# blackfin_e_lcd_keypad.net
KiCad netlist of a schematic drawn in Altium Designer
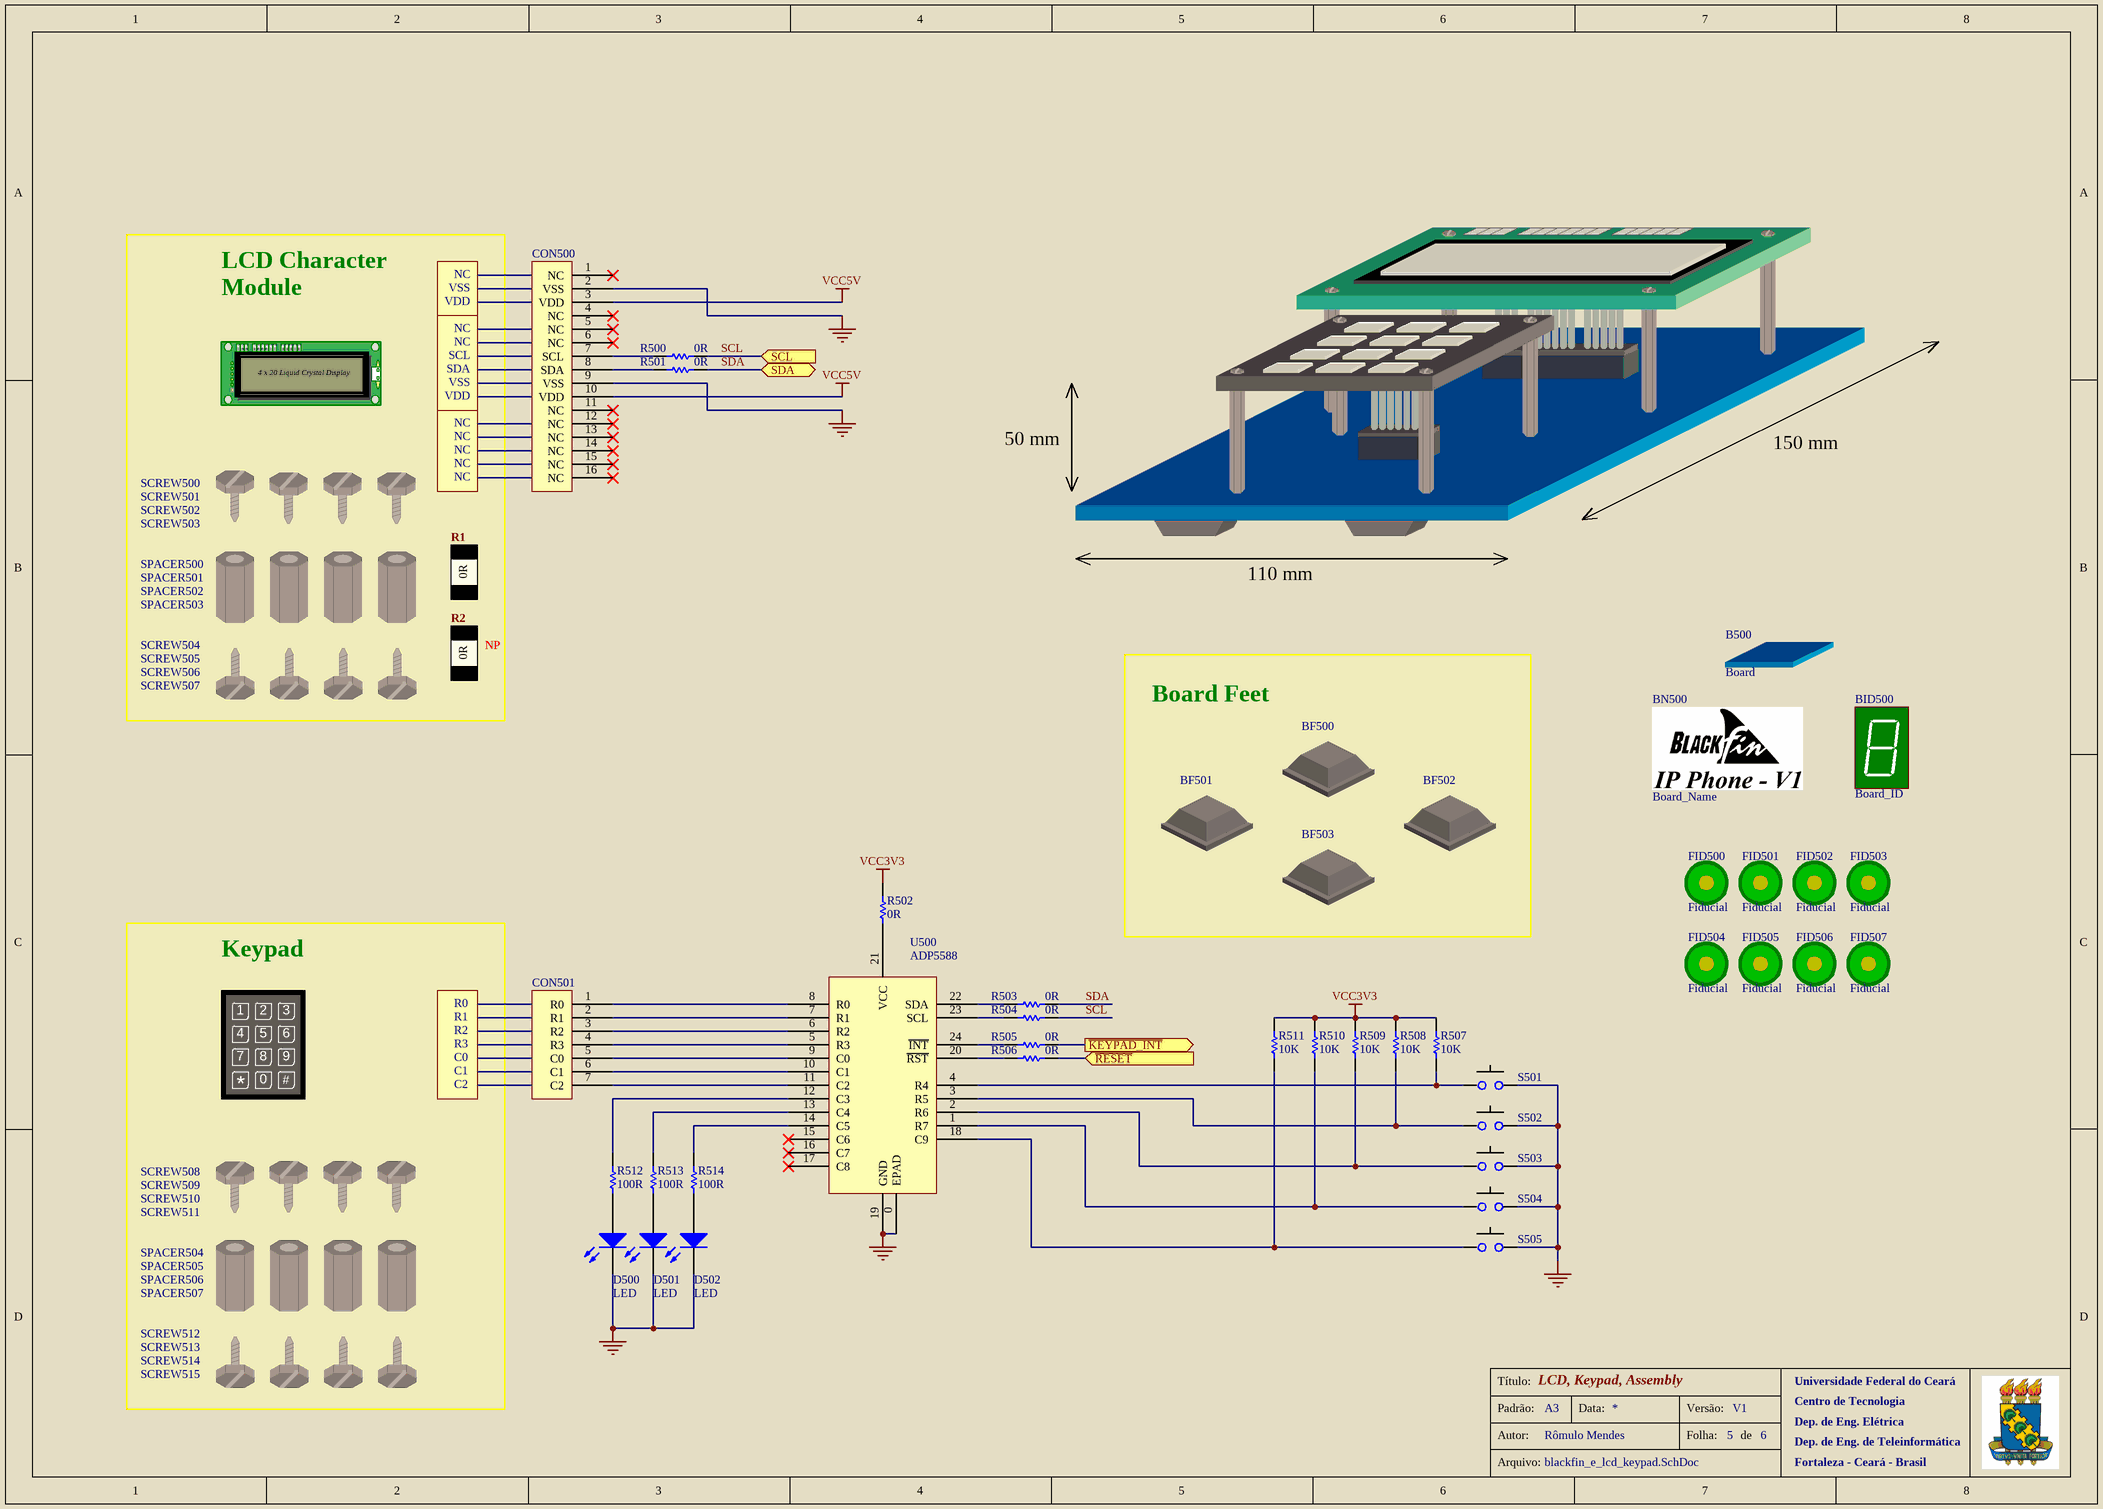
[diagram p0: blackfin_e_lcd_keypad.SchDoc]

(export (version "E")
  (design (tool "Eeschema 10.0.6"))
  (components
    (comp (ref "B500")
      (value "Board")
      (fields (field (name "EVENDORPART#") "NÃO SE APLICA"))
      (libsource (lib "blackfin_schlib") (part "Board"))
    )
    (comp (ref "BF500")
      (value "Board Foot")
      (footprint "blackfin_pcblib:Board Foot (Hemisphere)")
      (fields
        (field (name "EVENDORPART#") "517-SJ-5003BK")
        (field (name "PART#") "SJ-5003 (BLACK)")
        (field (name "MANUFACTURER") "3M Electronic Specialty")
      )
      (libsource (lib "*") (part "Board Foot"))
    )
    (comp (ref "BF501")
      (value "Board Foot")
      (footprint "blackfin_pcblib:Board Foot (Hemisphere)")
      (fields
        (field (name "EVENDORPART#") "517-SJ-5003BK")
        (field (name "PART#") "SJ-5003 (BLACK)")
        (field (name "MANUFACTURER") "3M Electronic Specialty")
      )
      (libsource (lib "*") (part "Board Foot"))
    )
    (comp (ref "BF502")
      (value "Board Foot")
      (footprint "blackfin_pcblib:Board Foot (Hemisphere)")
      (fields
        (field (name "EVENDORPART#") "517-SJ-5003BK")
        (field (name "PART#") "SJ-5003 (BLACK)")
        (field (name "MANUFACTURER") "3M Electronic Specialty")
      )
      (libsource (lib "*") (part "Board Foot"))
    )
    (comp (ref "BF503")
      (value "Board Foot")
      (footprint "blackfin_pcblib:Board Foot (Hemisphere)")
      (fields
        (field (name "EVENDORPART#") "517-SJ-5003BK")
        (field (name "PART#") "SJ-5003 (BLACK)")
        (field (name "MANUFACTURER") "3M Electronic Specialty")
      )
      (libsource (lib "*") (part "Board Foot"))
    )
    (comp (ref "BID500")
      (value "Board_ID")
      (footprint "blackfin_pcblib:BOARD_ID")
      (fields (field (name "EVENDORPART#") "NÃO SE APLICA"))
      (libsource (lib "blackfin_schlib") (part "Board_ID"))
    )
    (comp (ref "BN500")
      (value "Board_Name")
      (footprint "blackfin_pcblib:LOGO")
      (fields (field (name "EVENDORPART#") "NÃO SE APLICA"))
      (libsource (lib "blackfin_schlib") (part "Board_Name"))
    )
    (comp (ref "CON500")
      (value "LCD_Connector")
      (footprint "blackfin_pcblib:SOCKET_1x16")
      (fields (field (name "EVENDORPART#") "SSM-116-L-SV") (field (name "MANUFACTURER") "Samtec"))
      (libsource (lib "blackfin_schlib") (part "LCD_Connector"))
    )
    (comp (ref "CON501")
      (value "Keypad_Connector")
      (footprint "blackfin_pcblib:SOCKET_1x7")
      (fields (field (name "EVENDORPART#") "SSM-107-L-SV") (field (name "MANUFACTURER") "Samtec"))
      (libsource (lib "blackfin_schlib") (part "Keypad_Connector"))
    )
    (comp (ref "D500")
      (value "LED")
      (footprint "blackfin_pcblib:LED_0603")
      (description "Red LED")
      (fields (field (name "EVENDORPART#") "638-QTLP600C2TR") (field (name "MANUFACTURER") "Everlight"))
      (libsource (lib "blackfin_schlib") (part "LED"))
    )
    (comp (ref "D501")
      (value "LED")
      (footprint "blackfin_pcblib:LED_0603")
      (description "Red LED")
      (fields (field (name "EVENDORPART#") "638-QTLP600C2TR") (field (name "MANUFACTURER") "Everlight"))
      (libsource (lib "blackfin_schlib") (part "LED"))
    )
    (comp (ref "D502")
      (value "LED")
      (footprint "blackfin_pcblib:LED_0603")
      (description "Red LED")
      (fields (field (name "EVENDORPART#") "638-QTLP600C2TR") (field (name "MANUFACTURER") "Everlight"))
      (libsource (lib "blackfin_schlib") (part "LED"))
    )
    (comp (ref "FID500")
      (value "Fiducial")
      (footprint "blackfin_pcblib:Fiducial")
      (fields (field (name "EVENDORPART#") "NÃO SE APLICA"))
      (libsource (lib "blackfin_schlib") (part "Fiducial"))
    )
    (comp (ref "FID501")
      (value "Fiducial")
      (footprint "blackfin_pcblib:Fiducial")
      (fields (field (name "EVENDORPART#") "NÃO SE APLICA"))
      (libsource (lib "blackfin_schlib") (part "Fiducial"))
    )
    (comp (ref "FID502")
      (value "Fiducial")
      (footprint "blackfin_pcblib:Fiducial")
      (fields (field (name "EVENDORPART#") "NÃO SE APLICA"))
      (libsource (lib "blackfin_schlib") (part "Fiducial"))
    )
    (comp (ref "FID503")
      (value "Fiducial")
      (footprint "blackfin_pcblib:Fiducial")
      (fields (field (name "EVENDORPART#") "NÃO SE APLICA"))
      (libsource (lib "blackfin_schlib") (part "Fiducial"))
    )
    (comp (ref "FID504")
      (value "Fiducial")
      (footprint "blackfin_pcblib:Fiducial")
      (fields (field (name "EVENDORPART#") "NÃO SE APLICA"))
      (libsource (lib "blackfin_schlib") (part "Fiducial"))
    )
    (comp (ref "FID505")
      (value "Fiducial")
      (footprint "blackfin_pcblib:Fiducial")
      (fields (field (name "EVENDORPART#") "NÃO SE APLICA"))
      (libsource (lib "blackfin_schlib") (part "Fiducial"))
    )
    (comp (ref "FID506")
      (value "Fiducial")
      (footprint "blackfin_pcblib:Fiducial")
      (fields (field (name "EVENDORPART#") "NÃO SE APLICA"))
      (libsource (lib "blackfin_schlib") (part "Fiducial"))
    )
    (comp (ref "FID507")
      (value "Fiducial")
      (footprint "blackfin_pcblib:Fiducial")
      (fields (field (name "EVENDORPART#") "NÃO SE APLICA"))
      (libsource (lib "blackfin_schlib") (part "Fiducial"))
    )
    (comp (ref "KEYPAD_HEADER500")
      (value "Keypad_Header_1x7")
      (fields (field (name "EVENDORPART#") "ESQ-107-34-L-S") (field (name "MANUFACTURER") "Samtec"))
      (libsource (lib "blackfin_schlib") (part "Keypad_Header_1x7"))
    )
    (comp (ref "LCD500")
      (value "LCD")
      (footprint "blackfin_pcblib:LCD")
      (fields
        (field (name "EVENDORPART#") "763-0420D3Z-FL-GBW")
        (field (name "PART#") "NHD-0420D3Z-FL-GBW")
        (field (name "MANUFACTURER") "Newhaven")
      )
      (libsource (lib "*") (part "LCD"))
    )
    (comp (ref "LCD_HEADER500")
      (value "LCD_Header_1x3")
      (fields (field (name "EVENDORPART#") "DW-03-12-F-S-694") (field (name "MANUFACTURER") "Samtec"))
      (libsource (lib "blackfin_schlib") (part "LCD_Header_1x3"))
    )
    (comp (ref "LCD_HEADER501")
      (value "LCD_Header_1x6")
      (fields (field (name "EVENDORPART#") "DW-06-12-F-S-694") (field (name "MANUFACTURER") "Samtec"))
      (libsource (lib "blackfin_schlib") (part "LCD_Header_1x6"))
    )
    (comp (ref "LCD_HEADER502")
      (value "LCD_Header_1x5")
      (fields (field (name "EVENDORPART#") "DW-05-12-F-S-694") (field (name "MANUFACTURER") "Samtec"))
      (libsource (lib "blackfin_schlib") (part "LCD_Header_1x5"))
    )
    (comp (ref "LCD_RES500")
      (value "LCD_Resistor")
      (fields
        (field (name "EVENDORPART#") "71-CRCW0805-0-E3")
        (field (name "MANUFACTURER") "Vishay/Dale")
        (field (name "PART#") "CRCW08050000Z0EA")
      )
      (libsource (lib "blackfin_schlib") (part "LCD_Resistor"))
    )
    (comp (ref "LCD_RES501")
      (value "LCD_Resistor")
      (fields
        (field (name "EVENDORPART#") "71-CRCW0805-0-E3")
        (field (name "MANUFACTURER") "Vishay/Dale")
        (field (name "PART#") "CRCW08050000Z0EA")
      )
      (libsource (lib "blackfin_schlib") (part "LCD_Resistor"))
    )
    (comp (ref "R500")
      (value "0R")
      (footprint "blackfin_pcblib:R_0603")
      (fields
        (field (name "EVENDORPART#") "71-CRCW06030000Z0EB")
        (field (name "PART#") "CRCW06030000Z0EB")
        (field (name "MANUFACTURER") "Vishay/Dale")
      )
      (libsource (lib "blackfin_schlib") (part "Resistor"))
    )
    (comp (ref "R501")
      (value "0R")
      (footprint "blackfin_pcblib:R_0603")
      (fields
        (field (name "EVENDORPART#") "71-CRCW06030000Z0EB")
        (field (name "PART#") "CRCW06030000Z0EB")
        (field (name "MANUFACTURER") "Vishay/Dale")
      )
      (libsource (lib "blackfin_schlib") (part "Resistor"))
    )
    (comp (ref "R502")
      (value "0R")
      (footprint "blackfin_pcblib:R_0603")
      (fields
        (field (name "EVENDORPART#") "71-CRCW06030000Z0EB")
        (field (name "PART#") "CRCW06030000Z0EB")
        (field (name "MANUFACTURER") "Vishay/Dale")
      )
      (libsource (lib "blackfin_schlib") (part "Resistor"))
    )
    (comp (ref "R503")
      (value "0R")
      (footprint "blackfin_pcblib:R_0603")
      (fields
        (field (name "EVENDORPART#") "71-CRCW06030000Z0EB")
        (field (name "PART#") "CRCW06030000Z0EB")
        (field (name "MANUFACTURER") "Vishay/Dale")
      )
      (libsource (lib "blackfin_schlib") (part "Resistor"))
    )
    (comp (ref "R504")
      (value "0R")
      (footprint "blackfin_pcblib:R_0603")
      (fields
        (field (name "EVENDORPART#") "71-CRCW06030000Z0EB")
        (field (name "PART#") "CRCW06030000Z0EB")
        (field (name "MANUFACTURER") "Vishay/Dale")
      )
      (libsource (lib "blackfin_schlib") (part "Resistor"))
    )
    (comp (ref "R505")
      (value "0R")
      (footprint "blackfin_pcblib:R_0603")
      (fields
        (field (name "EVENDORPART#") "71-CRCW06030000Z0EB")
        (field (name "PART#") "CRCW06030000Z0EB")
        (field (name "MANUFACTURER") "Vishay/Dale")
      )
      (libsource (lib "blackfin_schlib") (part "Resistor"))
    )
    (comp (ref "R506")
      (value "0R")
      (footprint "blackfin_pcblib:R_0603")
      (fields
        (field (name "EVENDORPART#") "71-CRCW06030000Z0EB")
        (field (name "PART#") "CRCW06030000Z0EB")
        (field (name "MANUFACTURER") "Vishay/Dale")
      )
      (libsource (lib "blackfin_schlib") (part "Resistor"))
    )
    (comp (ref "R507")
      (value "10K")
      (footprint "blackfin_pcblib:R_0603")
      (fields
        (field (name "EVENDORPART#") "71-CRCW0603-10K-E3")
        (field (name "PART#") "CRCW060310K0FKEA")
        (field (name "MANUFACTURER") "Vishay/Dale")
      )
      (libsource (lib "blackfin_schlib") (part "Resistor"))
    )
    (comp (ref "R508")
      (value "10K")
      (footprint "blackfin_pcblib:R_0603")
      (fields
        (field (name "EVENDORPART#") "71-CRCW0603-10K-E3")
        (field (name "PART#") "CRCW060310K0FKEA")
        (field (name "MANUFACTURER") "Vishay/Dale")
      )
      (libsource (lib "blackfin_schlib") (part "Resistor"))
    )
    (comp (ref "R509")
      (value "10K")
      (footprint "blackfin_pcblib:R_0603")
      (fields
        (field (name "EVENDORPART#") "71-CRCW0603-10K-E3")
        (field (name "PART#") "CRCW060310K0FKEA")
        (field (name "MANUFACTURER") "Vishay/Dale")
      )
      (libsource (lib "blackfin_schlib") (part "Resistor"))
    )
    (comp (ref "R510")
      (value "10K")
      (footprint "blackfin_pcblib:R_0603")
      (fields
        (field (name "EVENDORPART#") "71-CRCW0603-10K-E3")
        (field (name "PART#") "CRCW060310K0FKEA")
        (field (name "MANUFACTURER") "Vishay/Dale")
      )
      (libsource (lib "blackfin_schlib") (part "Resistor"))
    )
    (comp (ref "R511")
      (value "10K")
      (footprint "blackfin_pcblib:R_0603")
      (fields
        (field (name "EVENDORPART#") "71-CRCW0603-10K-E3")
        (field (name "PART#") "CRCW060310K0FKEA")
        (field (name "MANUFACTURER") "Vishay/Dale")
      )
      (libsource (lib "blackfin_schlib") (part "Resistor"))
    )
    (comp (ref "R512")
      (value "100R")
      (footprint "blackfin_pcblib:R_0603")
      (fields
        (field (name "EVENDORPART#") "71-CRCW0603-100-E3")
        (field (name "PART#") "CRCW0603100RFKEA")
        (field (name "MANUFACTURER") "Vishay/Dale")
      )
      (libsource (lib "blackfin_schlib") (part "Resistor"))
    )
    (comp (ref "R513")
      (value "100R")
      (footprint "blackfin_pcblib:R_0603")
      (fields
        (field (name "EVENDORPART#") "71-CRCW0603-100-E3")
        (field (name "PART#") "CRCW0603100RFKEA")
        (field (name "MANUFACTURER") "Vishay/Dale")
      )
      (libsource (lib "blackfin_schlib") (part "Resistor"))
    )
    (comp (ref "R514")
      (value "100R")
      (footprint "blackfin_pcblib:R_0603")
      (fields
        (field (name "EVENDORPART#") "71-CRCW0603-100-E3")
        (field (name "PART#") "CRCW0603100RFKEA")
        (field (name "MANUFACTURER") "Vishay/Dale")
      )
      (libsource (lib "blackfin_schlib") (part "Resistor"))
    )
    (comp (ref "S500")
      (value "Keypad")
      (footprint "blackfin_pcblib:Keypad")
      (fields
        (field (name "EVENDORPART#") "GH5009-ND")
        (field (name "PART#") "96AB2-152-R")
        (field (name "MANUFACTURER") "Grayhill Inc")
      )
      (libsource (lib "blackfin_schlib") (part "Keypad"))
    )
    (comp (ref "S501")
      (value "Push Button")
      (footprint "blackfin_pcblib:Push Button")
      (fields
        (field (name "EVENDORPART#") "611-PTS645SH50SMTRLF")
        (field (name "PART#") "PTS645SH50SMTRLFS")
        (field (name "MANUFACTURER") "C&K Components")
      )
      (libsource (lib "*") (part "Push Button"))
    )
    (comp (ref "S502")
      (value "Push Button")
      (footprint "blackfin_pcblib:Push Button")
      (fields
        (field (name "EVENDORPART#") "611-PTS645SH50SMTRLF")
        (field (name "PART#") "PTS645SH50SMTRLFS")
        (field (name "MANUFACTURER") "C&K Components")
      )
      (libsource (lib "*") (part "Push Button"))
    )
    (comp (ref "S503")
      (value "Push Button")
      (footprint "blackfin_pcblib:Push Button")
      (fields
        (field (name "EVENDORPART#") "611-PTS645SH50SMTRLF")
        (field (name "PART#") "PTS645SH50SMTRLFS")
        (field (name "MANUFACTURER") "C&K Components")
      )
      (libsource (lib "*") (part "Push Button"))
    )
    (comp (ref "S504")
      (value "Push Button")
      (footprint "blackfin_pcblib:Push Button")
      (fields
        (field (name "EVENDORPART#") "611-PTS645SH50SMTRLF")
        (field (name "PART#") "PTS645SH50SMTRLFS")
        (field (name "MANUFACTURER") "C&K Components")
      )
      (libsource (lib "*") (part "Push Button"))
    )
    (comp (ref "S505")
      (value "Push Button")
      (footprint "blackfin_pcblib:Push Button")
      (fields
        (field (name "EVENDORPART#") "611-PTS645SH50SMTRLF")
        (field (name "PART#") "PTS645SH50SMTRLFS")
        (field (name "MANUFACTURER") "C&K Components")
      )
      (libsource (lib "*") (part "Push Button"))
    )
    (comp (ref "SCREW500")
      (value "Screw")
      (fields
        (field (name "EVENDORPART#") "534-29301")
        (field (name "PART#") "29301")
        (field (name "MANUFACTURER") "Keystone Electronics")
      )
      (libsource (lib "*") (part "Screw"))
    )
    (comp (ref "SCREW501")
      (value "Screw")
      (fields
        (field (name "EVENDORPART#") "534-29301")
        (field (name "PART#") "29301")
        (field (name "MANUFACTURER") "Keystone Electronics")
      )
      (libsource (lib "*") (part "Screw"))
    )
    (comp (ref "SCREW502")
      (value "Screw")
      (fields
        (field (name "EVENDORPART#") "534-29301")
        (field (name "PART#") "29301")
        (field (name "MANUFACTURER") "Keystone Electronics")
      )
      (libsource (lib "*") (part "Screw"))
    )
    (comp (ref "SCREW503")
      (value "Screw")
      (fields
        (field (name "EVENDORPART#") "534-29301")
        (field (name "PART#") "29301")
        (field (name "MANUFACTURER") "Keystone Electronics")
      )
      (libsource (lib "*") (part "Screw"))
    )
    (comp (ref "SCREW504")
      (value "Screw")
      (fields
        (field (name "EVENDORPART#") "534-29301")
        (field (name "PART#") "29301")
        (field (name "MANUFACTURER") "Keystone Electronics")
      )
      (libsource (lib "*") (part "Screw"))
    )
    (comp (ref "SCREW505")
      (value "Screw")
      (fields
        (field (name "EVENDORPART#") "534-29301")
        (field (name "PART#") "29301")
        (field (name "MANUFACTURER") "Keystone Electronics")
      )
      (libsource (lib "*") (part "Screw"))
    )
    (comp (ref "SCREW506")
      (value "Screw")
      (fields
        (field (name "EVENDORPART#") "534-29301")
        (field (name "PART#") "29301")
        (field (name "MANUFACTURER") "Keystone Electronics")
      )
      (libsource (lib "*") (part "Screw"))
    )
    (comp (ref "SCREW507")
      (value "Screw")
      (fields
        (field (name "EVENDORPART#") "534-29301")
        (field (name "PART#") "29301")
        (field (name "MANUFACTURER") "Keystone Electronics")
      )
      (libsource (lib "*") (part "Screw"))
    )
    (comp (ref "SCREW508")
      (value "Screw")
      (fields
        (field (name "EVENDORPART#") "534-29301")
        (field (name "PART#") "29301")
        (field (name "MANUFACTURER") "Keystone Electronics")
      )
      (libsource (lib "*") (part "Screw"))
    )
    (comp (ref "SCREW509")
      (value "Screw")
      (fields
        (field (name "EVENDORPART#") "534-29301")
        (field (name "PART#") "29301")
        (field (name "MANUFACTURER") "Keystone Electronics")
      )
      (libsource (lib "*") (part "Screw"))
    )
    (comp (ref "SCREW510")
      (value "Screw")
      (fields
        (field (name "EVENDORPART#") "534-29301")
        (field (name "PART#") "29301")
        (field (name "MANUFACTURER") "Keystone Electronics")
      )
      (libsource (lib "*") (part "Screw"))
    )
    (comp (ref "SCREW511")
      (value "Screw")
      (fields
        (field (name "EVENDORPART#") "534-29301")
        (field (name "PART#") "29301")
        (field (name "MANUFACTURER") "Keystone Electronics")
      )
      (libsource (lib "*") (part "Screw"))
    )
    (comp (ref "SCREW512")
      (value "Screw")
      (fields
        (field (name "EVENDORPART#") "534-29301")
        (field (name "PART#") "29301")
        (field (name "MANUFACTURER") "Keystone Electronics")
      )
      (libsource (lib "*") (part "Screw"))
    )
    (comp (ref "SCREW513")
      (value "Screw")
      (fields
        (field (name "EVENDORPART#") "534-29301")
        (field (name "PART#") "29301")
        (field (name "MANUFACTURER") "Keystone Electronics")
      )
      (libsource (lib "*") (part "Screw"))
    )
    (comp (ref "SCREW514")
      (value "Screw")
      (fields
        (field (name "EVENDORPART#") "534-29301")
        (field (name "PART#") "29301")
        (field (name "MANUFACTURER") "Keystone Electronics")
      )
      (libsource (lib "*") (part "Screw"))
    )
    (comp (ref "SCREW515")
      (value "Screw")
      (fields
        (field (name "EVENDORPART#") "534-29301")
        (field (name "PART#") "29301")
        (field (name "MANUFACTURER") "Keystone Electronics")
      )
      (libsource (lib "*") (part "Screw"))
    )
    (comp (ref "SPACER500")
      (value "Spacer")
      (fields
        (field (name "EVENDORPART#") "534-24428")
        (field (name "MANUFACTURER") "Keystone Electronics")
        (field (name "PART#") "24428")
      )
      (libsource (lib "blackfin_schlib") (part "Spacer"))
    )
    (comp (ref "SPACER501")
      (value "Spacer")
      (fields
        (field (name "EVENDORPART#") "534-24428")
        (field (name "MANUFACTURER") "Keystone Electronics")
        (field (name "PART#") "24428")
      )
      (libsource (lib "blackfin_schlib") (part "Spacer"))
    )
    (comp (ref "SPACER502")
      (value "Spacer")
      (fields
        (field (name "EVENDORPART#") "534-24428")
        (field (name "MANUFACTURER") "Keystone Electronics")
        (field (name "PART#") "24428")
      )
      (libsource (lib "blackfin_schlib") (part "Spacer"))
    )
    (comp (ref "SPACER503")
      (value "Spacer")
      (fields
        (field (name "EVENDORPART#") "534-24428")
        (field (name "MANUFACTURER") "Keystone Electronics")
        (field (name "PART#") "24428")
      )
      (libsource (lib "blackfin_schlib") (part "Spacer"))
    )
    (comp (ref "SPACER504")
      (value "Spacer")
      (fields
        (field (name "EVENDORPART#") "534-24428")
        (field (name "MANUFACTURER") "Keystone Electronics")
        (field (name "PART#") "24428")
      )
      (libsource (lib "blackfin_schlib") (part "Spacer"))
    )
    (comp (ref "SPACER505")
      (value "Spacer")
      (fields
        (field (name "EVENDORPART#") "534-24428")
        (field (name "MANUFACTURER") "Keystone Electronics")
        (field (name "PART#") "24428")
      )
      (libsource (lib "blackfin_schlib") (part "Spacer"))
    )
    (comp (ref "SPACER506")
      (value "Spacer")
      (fields
        (field (name "EVENDORPART#") "534-24428")
        (field (name "MANUFACTURER") "Keystone Electronics")
        (field (name "PART#") "24428")
      )
      (libsource (lib "blackfin_schlib") (part "Spacer"))
    )
    (comp (ref "SPACER507")
      (value "Spacer")
      (fields
        (field (name "EVENDORPART#") "534-24428")
        (field (name "MANUFACTURER") "Keystone Electronics")
        (field (name "PART#") "24428")
      )
      (libsource (lib "blackfin_schlib") (part "Spacer"))
    )
    (comp (ref "U500")
      (value "ADP5588")
      (footprint "blackfin_pcblib:QFN-24")
      (fields
        (field (name "EVENDORPART#") "ADP5588ACPZ-R7CT-ND")
        (field (name "PART#") "ADP5588ACPZ-R7")
        (field (name "MANUFACTURER") "Analog Devices")
      )
      (libsource (lib "blackfin_schlib") (part "ADP5588"))
    )
  )
  (nets
    (net (code "1") (name "/SCL") (class "Default")
      (node (ref "R500") (pin "2") (pinfunction "2_2") (pintype "passive"))
      (node (ref "R504") (pin "2") (pinfunction "2_2") (pintype "passive"))
    )
    (net (code "2") (name "/SDA") (class "Default")
      (node (ref "R501") (pin "2") (pinfunction "2_2") (pintype "passive"))
      (node (ref "R503") (pin "2") (pinfunction "2_2") (pintype "passive"))
    )
    (net (code "3") (name "/~{KEYPAD_INT}") (class "Default")
      (node (ref "R505") (pin "2") (pinfunction "2_2") (pintype "passive"))
    )
    (net (code "4") (name "/~{RESET}") (class "Default")
      (node (ref "R506") (pin "2") (pinfunction "2_2") (pintype "passive"))
    )
    (net (code "5") (name "GND") (class "Default")
      (node (ref "CON500") (pin "2") (pinfunction "VSS_2") (pintype "passive"))
      (node (ref "CON500") (pin "9") (pinfunction "VSS_9") (pintype "passive"))
      (node (ref "D500") (pin "2") (pinfunction "K_2") (pintype "passive"))
      (node (ref "D501") (pin "2") (pinfunction "K_2") (pintype "passive"))
      (node (ref "D502") (pin "2") (pinfunction "K_2") (pintype "passive"))
      (node (ref "S501") (pin "2") (pinfunction "2_2") (pintype "passive"))
      (node (ref "S502") (pin "2") (pinfunction "2_2") (pintype "passive"))
      (node (ref "S503") (pin "2") (pinfunction "2_2") (pintype "passive"))
      (node (ref "S504") (pin "2") (pinfunction "2_2") (pintype "passive"))
      (node (ref "S505") (pin "2") (pinfunction "2_2") (pintype "passive"))
      (node (ref "U500") (pin "0") (pinfunction "EPAD_0") (pintype "passive"))
      (node (ref "U500") (pin "19") (pinfunction "GND_19") (pintype "passive"))
    )
    (net (code "6") (name "Net-(CON500-SCL)") (class "Default")
      (node (ref "CON500") (pin "7") (pinfunction "SCL_7") (pintype "passive"))
      (node (ref "R500") (pin "1") (pinfunction "1_1") (pintype "passive"))
    )
    (net (code "7") (name "Net-(CON500-SDA)") (class "Default")
      (node (ref "CON500") (pin "8") (pinfunction "SDA_8") (pintype "passive"))
      (node (ref "R501") (pin "1") (pinfunction "1_1") (pintype "passive"))
    )
    (net (code "8") (name "Net-(CON501-C0)") (class "Default")
      (node (ref "CON501") (pin "5") (pinfunction "C0_5") (pintype "passive"))
      (node (ref "U500") (pin "9") (pinfunction "C0_9") (pintype "passive"))
    )
    (net (code "9") (name "Net-(CON501-C1)") (class "Default")
      (node (ref "CON501") (pin "6") (pinfunction "C1_6") (pintype "passive"))
      (node (ref "U500") (pin "10") (pinfunction "C1_10") (pintype "passive"))
    )
    (net (code "10") (name "Net-(CON501-C2)") (class "Default")
      (node (ref "CON501") (pin "7") (pinfunction "C2_7") (pintype "passive"))
      (node (ref "U500") (pin "11") (pinfunction "C2_11") (pintype "passive"))
    )
    (net (code "11") (name "Net-(CON501-R0)") (class "Default")
      (node (ref "CON501") (pin "1") (pinfunction "R0_1") (pintype "passive"))
      (node (ref "U500") (pin "8") (pinfunction "R0_8") (pintype "passive"))
    )
    (net (code "12") (name "Net-(CON501-R1)") (class "Default")
      (node (ref "CON501") (pin "2") (pinfunction "R1_2") (pintype "passive"))
      (node (ref "U500") (pin "7") (pinfunction "R1_7") (pintype "passive"))
    )
    (net (code "13") (name "Net-(CON501-R2)") (class "Default")
      (node (ref "CON501") (pin "3") (pinfunction "R2_3") (pintype "passive"))
      (node (ref "U500") (pin "6") (pinfunction "R2_6") (pintype "passive"))
    )
    (net (code "14") (name "Net-(CON501-R3)") (class "Default")
      (node (ref "CON501") (pin "4") (pinfunction "R3_4") (pintype "passive"))
      (node (ref "U500") (pin "5") (pinfunction "R3_5") (pintype "passive"))
    )
    (net (code "15") (name "Net-(D500-A)") (class "Default")
      (node (ref "D500") (pin "1") (pinfunction "A_1") (pintype "passive"))
      (node (ref "R512") (pin "1") (pinfunction "1_1") (pintype "passive"))
    )
    (net (code "16") (name "Net-(D501-A)") (class "Default")
      (node (ref "D501") (pin "1") (pinfunction "A_1") (pintype "passive"))
      (node (ref "R513") (pin "1") (pinfunction "1_1") (pintype "passive"))
    )
    (net (code "17") (name "Net-(D502-A)") (class "Default")
      (node (ref "D502") (pin "1") (pinfunction "A_1") (pintype "passive"))
      (node (ref "R514") (pin "1") (pinfunction "1_1") (pintype "passive"))
    )
    (net (code "18") (name "Net-(U500-C3)") (class "Default")
      (node (ref "R512") (pin "2") (pinfunction "2_2") (pintype "passive"))
      (node (ref "U500") (pin "12") (pinfunction "C3_12") (pintype "passive"))
    )
    (net (code "19") (name "Net-(U500-C4)") (class "Default")
      (node (ref "R513") (pin "2") (pinfunction "2_2") (pintype "passive"))
      (node (ref "U500") (pin "13") (pinfunction "C4_13") (pintype "passive"))
    )
    (net (code "20") (name "Net-(U500-C5)") (class "Default")
      (node (ref "R514") (pin "2") (pinfunction "2_2") (pintype "passive"))
      (node (ref "U500") (pin "14") (pinfunction "C5_14") (pintype "passive"))
    )
    (net (code "21") (name "Net-(U500-C9)") (class "Default")
      (node (ref "R511") (pin "2") (pinfunction "2_2") (pintype "passive"))
      (node (ref "S505") (pin "1") (pinfunction "1_1") (pintype "passive"))
      (node (ref "U500") (pin "18") (pinfunction "C9_18") (pintype "passive"))
    )
    (net (code "22") (name "Net-(U500-R4)") (class "Default")
      (node (ref "R507") (pin "2") (pinfunction "2_2") (pintype "passive"))
      (node (ref "S501") (pin "1") (pinfunction "1_1") (pintype "passive"))
      (node (ref "U500") (pin "4") (pinfunction "R4_4") (pintype "passive"))
    )
    (net (code "23") (name "Net-(U500-R5)") (class "Default")
      (node (ref "R508") (pin "2") (pinfunction "2_2") (pintype "passive"))
      (node (ref "S502") (pin "1") (pinfunction "1_1") (pintype "passive"))
      (node (ref "U500") (pin "3") (pinfunction "R5_3") (pintype "passive"))
    )
    (net (code "24") (name "Net-(U500-R6)") (class "Default")
      (node (ref "R509") (pin "2") (pinfunction "2_2") (pintype "passive"))
      (node (ref "S503") (pin "1") (pinfunction "1_1") (pintype "passive"))
      (node (ref "U500") (pin "2") (pinfunction "R6_2") (pintype "passive"))
    )
    (net (code "25") (name "Net-(U500-R7)") (class "Default")
      (node (ref "R510") (pin "2") (pinfunction "2_2") (pintype "passive"))
      (node (ref "S504") (pin "1") (pinfunction "1_1") (pintype "passive"))
      (node (ref "U500") (pin "1") (pinfunction "R7_1") (pintype "passive"))
    )
    (net (code "26") (name "Net-(U500-SCL)") (class "Default")
      (node (ref "R504") (pin "1") (pinfunction "1_1") (pintype "passive"))
      (node (ref "U500") (pin "23") (pinfunction "SCL_23") (pintype "passive"))
    )
    (net (code "27") (name "Net-(U500-SDA)") (class "Default")
      (node (ref "R503") (pin "1") (pinfunction "1_1") (pintype "passive"))
      (node (ref "U500") (pin "22") (pinfunction "SDA_22") (pintype "passive"))
    )
    (net (code "28") (name "Net-(U500-VCC)") (class "Default")
      (node (ref "R502") (pin "1") (pinfunction "1_1") (pintype "passive"))
      (node (ref "U500") (pin "21") (pinfunction "VCC_21") (pintype "passive"))
    )
    (net (code "29") (name "Net-(U500-~{INT})") (class "Default")
      (node (ref "R505") (pin "1") (pinfunction "1_1") (pintype "passive"))
      (node (ref "U500") (pin "24") (pinfunction "~{INT}_24") (pintype "passive"))
    )
    (net (code "30") (name "Net-(U500-~{RST})") (class "Default")
      (node (ref "R506") (pin "1") (pinfunction "1_1") (pintype "passive"))
      (node (ref "U500") (pin "20") (pinfunction "~{RST}_20") (pintype "passive"))
    )
    (net (code "31") (name "VCC3V3") (class "Default")
      (node (ref "R502") (pin "2") (pinfunction "2_2") (pintype "passive"))
      (node (ref "R507") (pin "1") (pinfunction "1_1") (pintype "passive"))
      (node (ref "R508") (pin "1") (pinfunction "1_1") (pintype "passive"))
      (node (ref "R509") (pin "1") (pinfunction "1_1") (pintype "passive"))
      (node (ref "R510") (pin "1") (pinfunction "1_1") (pintype "passive"))
      (node (ref "R511") (pin "1") (pinfunction "1_1") (pintype "passive"))
    )
    (net (code "32") (name "VCC5V") (class "Default")
      (node (ref "CON500") (pin "10") (pinfunction "VDD_10") (pintype "passive"))
      (node (ref "CON500") (pin "3") (pinfunction "VDD_3") (pintype "passive"))
    )
    (net (code "33") (name "unconnected-(CON500-NC-Pad1)") (class "Default")
      (node (ref "CON500") (pin "1") (pinfunction "NC_1") (pintype "passive+no_connect"))
    )
    (net (code "34") (name "unconnected-(CON500-NC-Pad4)") (class "Default")
      (node (ref "CON500") (pin "4") (pinfunction "NC_4") (pintype "passive+no_connect"))
    )
    (net (code "35") (name "unconnected-(CON500-NC-Pad5)") (class "Default")
      (node (ref "CON500") (pin "5") (pinfunction "NC_5") (pintype "passive+no_connect"))
    )
    (net (code "36") (name "unconnected-(CON500-NC-Pad6)") (class "Default")
      (node (ref "CON500") (pin "6") (pinfunction "NC_6") (pintype "passive+no_connect"))
    )
    (net (code "37") (name "unconnected-(CON500-NC-Pad11)") (class "Default")
      (node (ref "CON500") (pin "11") (pinfunction "NC_11") (pintype "passive+no_connect"))
    )
    (net (code "38") (name "unconnected-(CON500-NC-Pad12)") (class "Default")
      (node (ref "CON500") (pin "12") (pinfunction "NC_12") (pintype "passive+no_connect"))
    )
    (net (code "39") (name "unconnected-(CON500-NC-Pad13)") (class "Default")
      (node (ref "CON500") (pin "13") (pinfunction "NC_13") (pintype "passive+no_connect"))
    )
    (net (code "40") (name "unconnected-(CON500-NC-Pad14)") (class "Default")
      (node (ref "CON500") (pin "14") (pinfunction "NC_14") (pintype "passive+no_connect"))
    )
    (net (code "41") (name "unconnected-(CON500-NC-Pad15)") (class "Default")
      (node (ref "CON500") (pin "15") (pinfunction "NC_15") (pintype "passive+no_connect"))
    )
    (net (code "42") (name "unconnected-(CON500-NC-Pad16)") (class "Default")
      (node (ref "CON500") (pin "16") (pinfunction "NC_16") (pintype "passive+no_connect"))
    )
    (net (code "43") (name "unconnected-(U500-C6-Pad15)") (class "Default")
      (node (ref "U500") (pin "15") (pinfunction "C6_15") (pintype "passive+no_connect"))
    )
    (net (code "44") (name "unconnected-(U500-C7-Pad16)") (class "Default")
      (node (ref "U500") (pin "16") (pinfunction "C7_16") (pintype "passive+no_connect"))
    )
    (net (code "45") (name "unconnected-(U500-C8-Pad17)") (class "Default")
      (node (ref "U500") (pin "17") (pinfunction "C8_17") (pintype "passive+no_connect"))
    )
  )
)
